# FPGAPower_Misc.net
KiCad netlist of a schematic drawn in Altium Designer
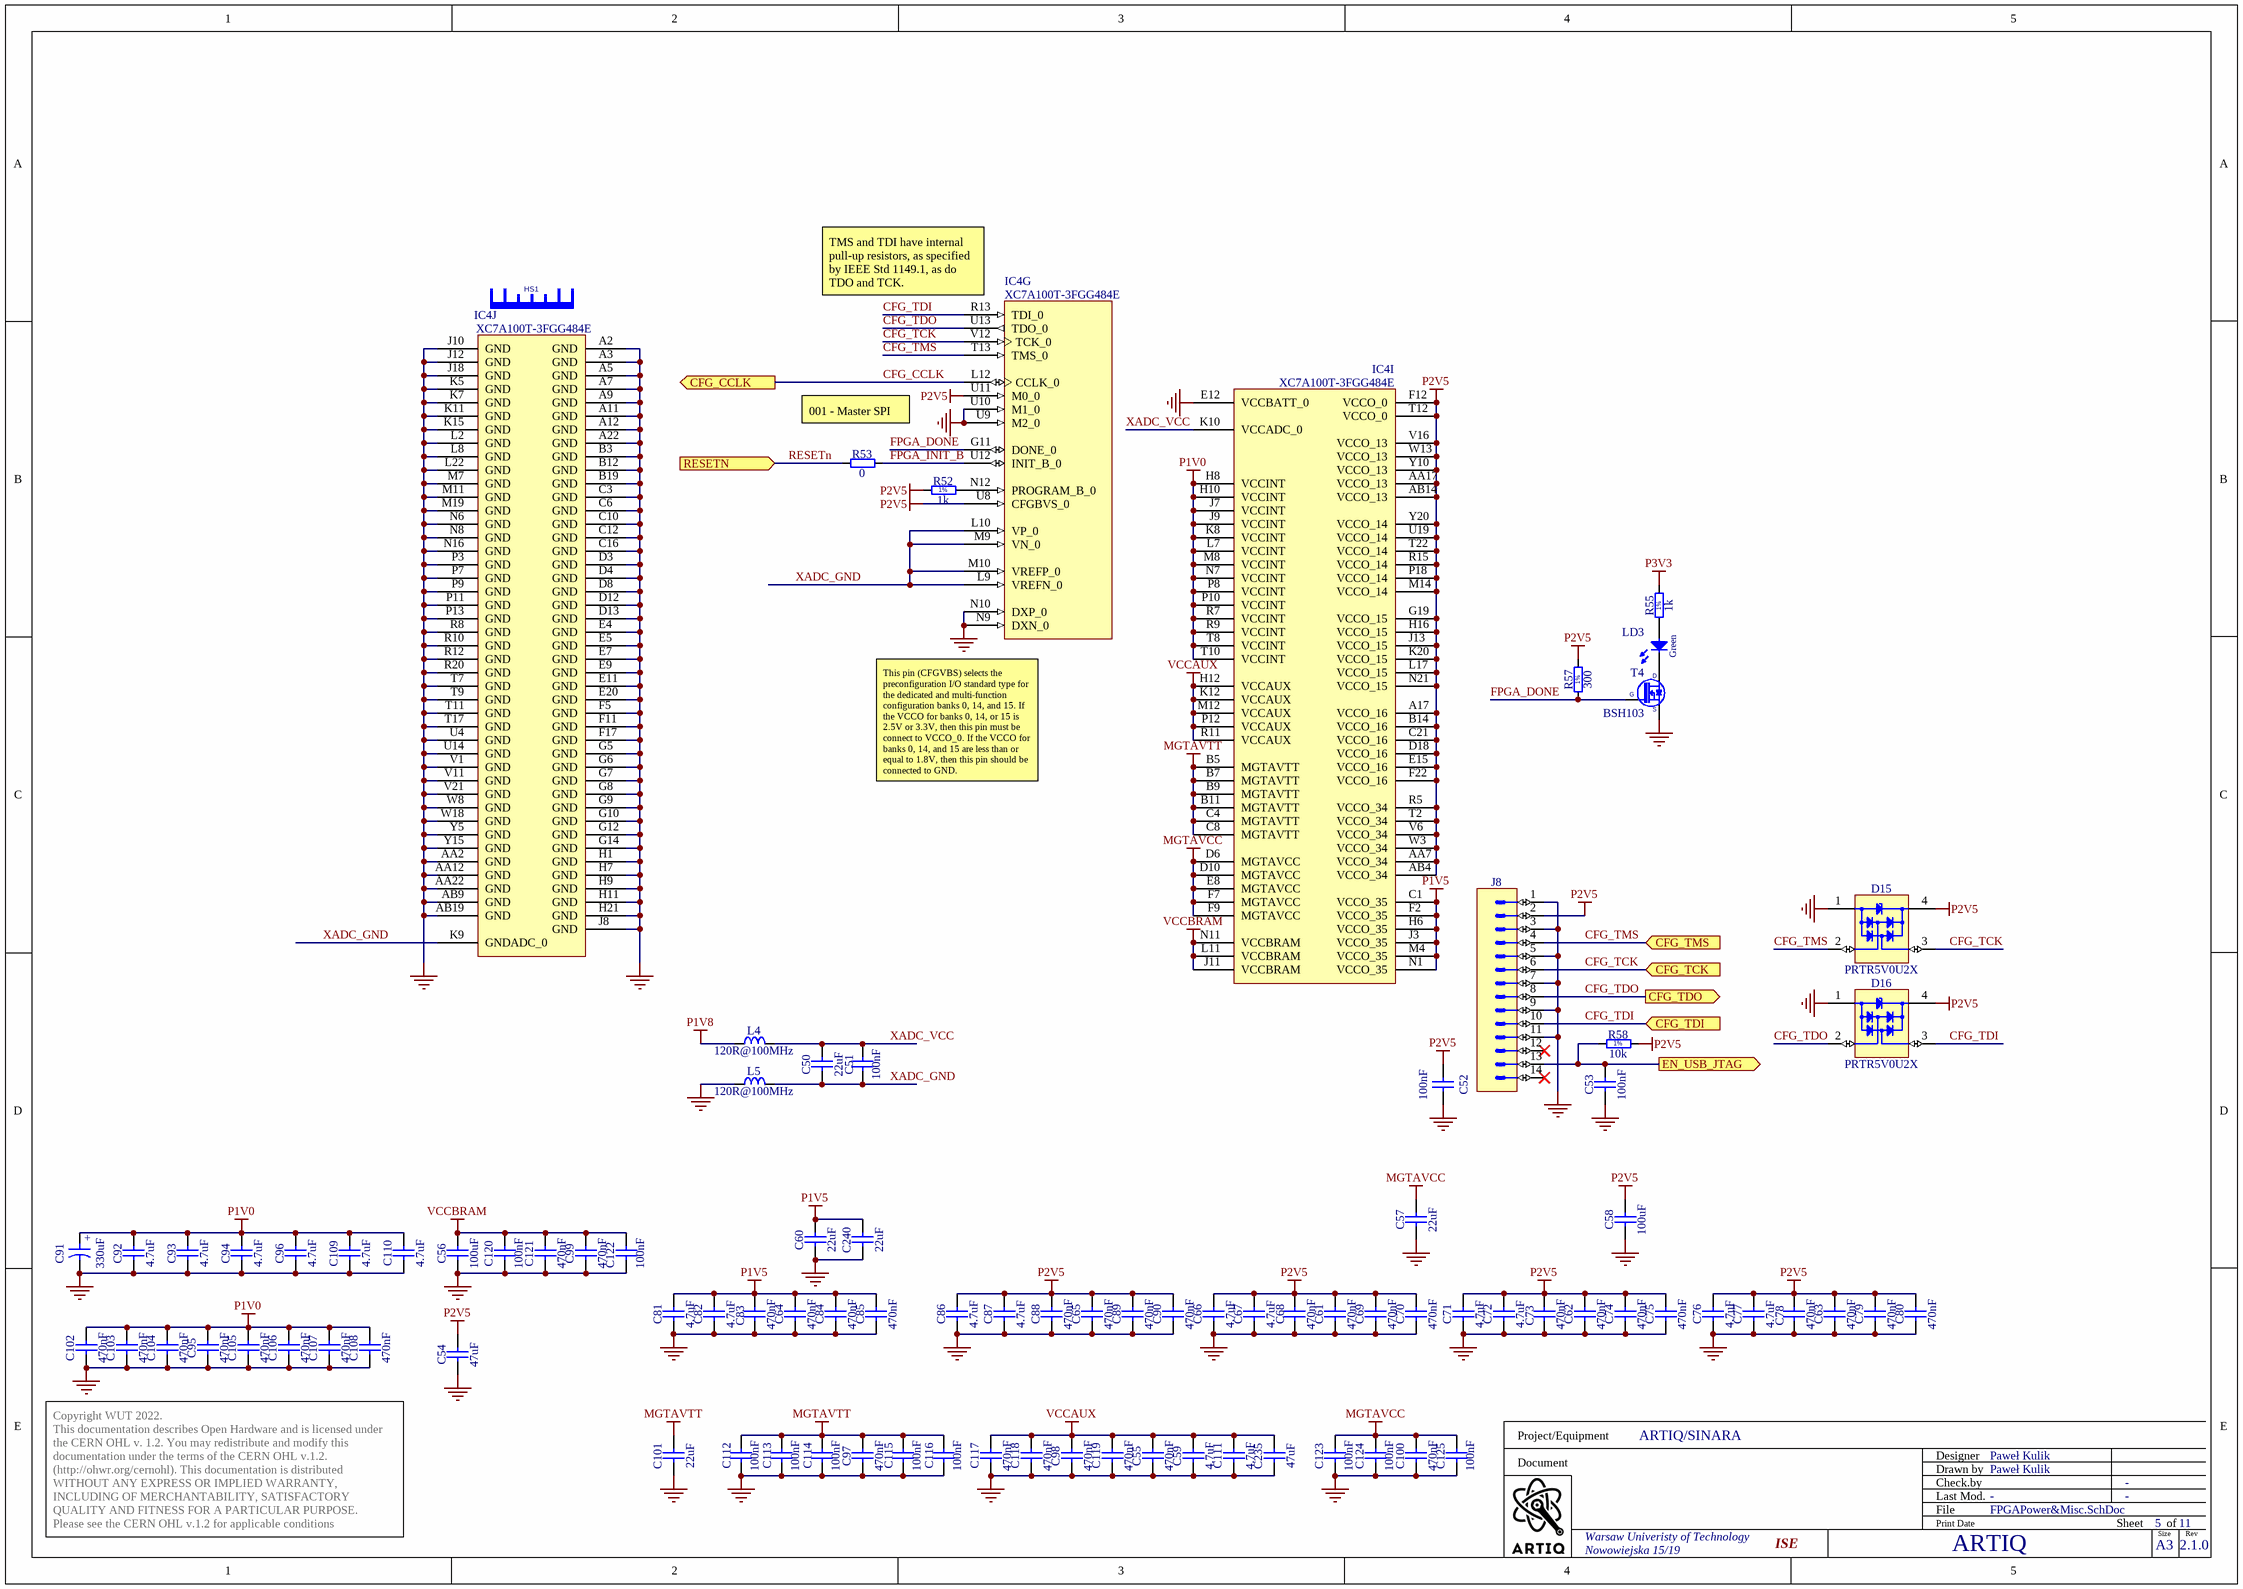
[diagram p0: FPGAPower&Misc.SchDoc]

(export (version "E")
  (design (tool "Eeschema 10.0.6"))
  (components
    (comp (ref "C50")
      (value "22uF")
      (footprint "CAPC1709X100N")
      (description "Non-polarised capacitor")
      (fields
        (field (name "PART NUMBER") "CC0603_22UF_6.3V_20%_X5R")
        (field (name "VOLTAGE") "6.3V")
        (field (name "AUTHOR") "CERN DEM JLC")
      )
      (libsource (lib "Capacitors") (part "Capacitor - non polarized"))
    )
    (comp (ref "C51")
      (value "100nF")
      (footprint "CAPC0603X33N")
      (description "Non-polarised capacitor")
      (fields
        (field (name "PART NUMBER") "CC0201_100NF_6.3V_10%_X5R")
        (field (name "VOLTAGE") "6.3V")
        (field (name "AUTHOR") "CERN DEM JLC")
      )
      (libsource (lib "Capacitors") (part "Capacitor - non polarized"))
    )
    (comp (ref "C52")
      (value "100nF")
      (footprint "CAPC0603X33N")
      (description "Non-polarised capacitor")
      (fields
        (field (name "PART NUMBER") "CC0201_100NF_6.3V_10%_X5R")
        (field (name "VOLTAGE") "6.3V")
        (field (name "AUTHOR") "CERN DEM JLC")
      )
      (libsource (lib "Capacitors") (part "Capacitor - non polarized"))
    )
    (comp (ref "C53")
      (value "100nF")
      (footprint "CAPC0603X33N")
      (description "Non-polarised capacitor")
      (fields
        (field (name "PART NUMBER") "CC0201_100NF_6.3V_10%_X5R")
        (field (name "VOLTAGE") "6.3V")
        (field (name "AUTHOR") "CERN DEM JLC")
      )
      (libsource (lib "Capacitors") (part "Capacitor - non polarized"))
    )
    (comp (ref "C54")
      (value "47uF")
      (footprint "CAPC3225X270N")
      (description "Non-polarised capacitor")
      (fields
        (field (name "PART NUMBER") "CC1210_47UF_10V_10%_X7R")
        (field (name "VOLTAGE") "10V")
        (field (name "AUTHOR") "CERN DEM BC")
      )
      (libsource (lib "Capacitors") (part "Capacitor - non polarized"))
    )
    (comp (ref "C55")
      (value "470nF")
      (footprint "CAPC0603X33N")
      (description "Non-polarised capacitor")
      (fields
        (field (name "PART NUMBER") "CC0201_470NF_4V_20%_X5R")
        (field (name "VOLTAGE") "4V")
        (field (name "AUTHOR") "CERN DEM JLC")
      )
      (libsource (lib "Capacitors") (part "Capacitor - non polarized"))
    )
    (comp (ref "C56")
      (value "100uF")
      (footprint "CAPC3225X270N")
      (description "Non-polarised capacitor")
      (fields
        (field (name "PART NUMBER") "CC1210_100UF_6.3V_20%_X5R")
        (field (name "VOLTAGE") "6.3V")
        (field (name "AUTHOR") "CERN DEM JLC")
      )
      (libsource (lib "Capacitors") (part "Capacitor - non polarized"))
    )
    (comp (ref "C57")
      (value "22uF")
      (footprint "CAPC1709X100N")
      (description "Non-polarised capacitor")
      (fields
        (field (name "PART NUMBER") "CC0603_22UF_6.3V_20%_X5R")
        (field (name "VOLTAGE") "6.3V")
        (field (name "AUTHOR") "CERN DEM JLC")
      )
      (libsource (lib "Capacitors") (part "Capacitor - non polarized"))
    )
    (comp (ref "C58")
      (value "100uF")
      (footprint "CAPC3225X270N")
      (description "Non-polarised capacitor")
      (fields
        (field (name "PART NUMBER") "CC1210_100UF_6.3V_20%_X5R")
        (field (name "VOLTAGE") "6.3V")
        (field (name "AUTHOR") "CERN DEM JLC")
      )
      (libsource (lib "Capacitors") (part "Capacitor - non polarized"))
    )
    (comp (ref "C59")
      (value "4.7uF")
      (footprint "CAPC2012X135N")
      (description "Non-polarised capacitor")
      (fields
        (field (name "MANUFACTURER") "GENERIC")
        (field (name "PART NUMBER") "CC0805_4.7UF_10V_10%_X5R")
        (field (name "AUTHOR") "CERN DEM JLC")
      )
      (libsource (lib "Capacitors") (part "Capacitor - non polarized"))
    )
    (comp (ref "C60")
      (value "22uF")
      (footprint "CAPC1709X100N")
      (description "Non-polarised capacitor")
      (fields
        (field (name "PART NUMBER") "CC0603_22UF_6.3V_20%_X5R")
        (field (name "VOLTAGE") "6.3V")
        (field (name "AUTHOR") "CERN DEM JLC")
      )
      (libsource (lib "Capacitors") (part "Capacitor - non polarized"))
    )
    (comp (ref "C61")
      (value "470nF")
      (footprint "CAPC0603X33N")
      (description "Non-polarised capacitor")
      (fields
        (field (name "PART NUMBER") "CC0201_470NF_4V_20%_X5R")
        (field (name "VOLTAGE") "4V")
        (field (name "AUTHOR") "CERN DEM JLC")
      )
      (libsource (lib "Capacitors") (part "Capacitor - non polarized"))
    )
    (comp (ref "C62")
      (value "470nF")
      (footprint "CAPC0603X33N")
      (description "Non-polarised capacitor")
      (fields
        (field (name "PART NUMBER") "CC0201_470NF_4V_20%_X5R")
        (field (name "VOLTAGE") "4V")
        (field (name "AUTHOR") "CERN DEM JLC")
      )
      (libsource (lib "Capacitors") (part "Capacitor - non polarized"))
    )
    (comp (ref "C63")
      (value "470nF")
      (footprint "CAPC0603X33N")
      (description "Non-polarised capacitor")
      (fields
        (field (name "PART NUMBER") "CC0201_470NF_4V_20%_X5R")
        (field (name "VOLTAGE") "4V")
        (field (name "AUTHOR") "CERN DEM JLC")
      )
      (libsource (lib "Capacitors") (part "Capacitor - non polarized"))
    )
    (comp (ref "C64")
      (value "470nF")
      (footprint "CAPC0603X33N")
      (description "Non-polarised capacitor")
      (fields
        (field (name "PART NUMBER") "CC0201_470NF_4V_20%_X5R")
        (field (name "VOLTAGE") "4V")
        (field (name "AUTHOR") "CERN DEM JLC")
      )
      (libsource (lib "Capacitors") (part "Capacitor - non polarized"))
    )
    (comp (ref "C65")
      (value "470nF")
      (footprint "CAPC0603X33N")
      (description "Non-polarised capacitor")
      (fields
        (field (name "PART NUMBER") "CC0201_470NF_4V_20%_X5R")
        (field (name "VOLTAGE") "4V")
        (field (name "AUTHOR") "CERN DEM JLC")
      )
      (libsource (lib "Capacitors") (part "Capacitor - non polarized"))
    )
    (comp (ref "C66")
      (value "4.7uF")
      (footprint "CAPC2012X135N")
      (description "Non-polarised capacitor")
      (fields
        (field (name "MANUFACTURER") "GENERIC")
        (field (name "PART NUMBER") "CC0805_4.7UF_10V_10%_X5R")
        (field (name "AUTHOR") "CERN DEM JLC")
      )
      (libsource (lib "Capacitors") (part "Capacitor - non polarized"))
    )
    (comp (ref "C67")
      (value "4.7uF")
      (footprint "CAPC2012X135N")
      (description "Non-polarised capacitor")
      (fields
        (field (name "MANUFACTURER") "GENERIC")
        (field (name "PART NUMBER") "CC0805_4.7UF_10V_10%_X5R")
        (field (name "AUTHOR") "CERN DEM JLC")
      )
      (libsource (lib "Capacitors") (part "Capacitor - non polarized"))
    )
    (comp (ref "C68")
      (value "470nF")
      (footprint "CAPC0603X33N")
      (description "Non-polarised capacitor")
      (fields
        (field (name "PART NUMBER") "CC0201_470NF_4V_20%_X5R")
        (field (name "VOLTAGE") "4V")
        (field (name "AUTHOR") "CERN DEM JLC")
      )
      (libsource (lib "Capacitors") (part "Capacitor - non polarized"))
    )
    (comp (ref "C69")
      (value "470nF")
      (footprint "CAPC0603X33N")
      (description "Non-polarised capacitor")
      (fields
        (field (name "PART NUMBER") "CC0201_470NF_4V_20%_X5R")
        (field (name "VOLTAGE") "4V")
        (field (name "AUTHOR") "CERN DEM JLC")
      )
      (libsource (lib "Capacitors") (part "Capacitor - non polarized"))
    )
    (comp (ref "C70")
      (value "470nF")
      (footprint "CAPC0603X33N")
      (description "Non-polarised capacitor")
      (fields
        (field (name "PART NUMBER") "CC0201_470NF_4V_20%_X5R")
        (field (name "VOLTAGE") "4V")
        (field (name "AUTHOR") "CERN DEM JLC")
      )
      (libsource (lib "Capacitors") (part "Capacitor - non polarized"))
    )
    (comp (ref "C71")
      (value "4.7uF")
      (footprint "CAPC2012X135N")
      (description "Non-polarised capacitor")
      (fields
        (field (name "MANUFACTURER") "GENERIC")
        (field (name "PART NUMBER") "CC0805_4.7UF_10V_10%_X5R")
        (field (name "AUTHOR") "CERN DEM JLC")
      )
      (libsource (lib "Capacitors") (part "Capacitor - non polarized"))
    )
    (comp (ref "C72")
      (value "4.7uF")
      (footprint "CAPC2012X135N")
      (description "Non-polarised capacitor")
      (fields
        (field (name "MANUFACTURER") "GENERIC")
        (field (name "PART NUMBER") "CC0805_4.7UF_10V_10%_X5R")
        (field (name "AUTHOR") "CERN DEM JLC")
      )
      (libsource (lib "Capacitors") (part "Capacitor - non polarized"))
    )
    (comp (ref "C73")
      (value "470nF")
      (footprint "CAPC0603X33N")
      (description "Non-polarised capacitor")
      (fields
        (field (name "PART NUMBER") "CC0201_470NF_4V_20%_X5R")
        (field (name "VOLTAGE") "4V")
        (field (name "AUTHOR") "CERN DEM JLC")
      )
      (libsource (lib "Capacitors") (part "Capacitor - non polarized"))
    )
    (comp (ref "C74")
      (value "470nF")
      (footprint "CAPC0603X33N")
      (description "Non-polarised capacitor")
      (fields
        (field (name "PART NUMBER") "CC0201_470NF_4V_20%_X5R")
        (field (name "VOLTAGE") "4V")
        (field (name "AUTHOR") "CERN DEM JLC")
      )
      (libsource (lib "Capacitors") (part "Capacitor - non polarized"))
    )
    (comp (ref "C75")
      (value "470nF")
      (footprint "CAPC0603X33N")
      (description "Non-polarised capacitor")
      (fields
        (field (name "PART NUMBER") "CC0201_470NF_4V_20%_X5R")
        (field (name "VOLTAGE") "4V")
        (field (name "AUTHOR") "CERN DEM JLC")
      )
      (libsource (lib "Capacitors") (part "Capacitor - non polarized"))
    )
    (comp (ref "C76")
      (value "4.7uF")
      (footprint "CAPC2012X135N")
      (description "Non-polarised capacitor")
      (fields
        (field (name "MANUFACTURER") "GENERIC")
        (field (name "PART NUMBER") "CC0805_4.7UF_10V_10%_X5R")
        (field (name "AUTHOR") "CERN DEM JLC")
      )
      (libsource (lib "Capacitors") (part "Capacitor - non polarized"))
    )
    (comp (ref "C77")
      (value "4.7uF")
      (footprint "CAPC2012X135N")
      (description "Non-polarised capacitor")
      (fields
        (field (name "MANUFACTURER") "GENERIC")
        (field (name "PART NUMBER") "CC0805_4.7UF_10V_10%_X5R")
        (field (name "AUTHOR") "CERN DEM JLC")
      )
      (libsource (lib "Capacitors") (part "Capacitor - non polarized"))
    )
    (comp (ref "C78")
      (value "470nF")
      (footprint "CAPC0603X33N")
      (description "Non-polarised capacitor")
      (fields
        (field (name "PART NUMBER") "CC0201_470NF_4V_20%_X5R")
        (field (name "VOLTAGE") "4V")
        (field (name "AUTHOR") "CERN DEM JLC")
      )
      (libsource (lib "Capacitors") (part "Capacitor - non polarized"))
    )
    (comp (ref "C79")
      (value "470nF")
      (footprint "CAPC0603X33N")
      (description "Non-polarised capacitor")
      (fields
        (field (name "PART NUMBER") "CC0201_470NF_4V_20%_X5R")
        (field (name "VOLTAGE") "4V")
        (field (name "AUTHOR") "CERN DEM JLC")
      )
      (libsource (lib "Capacitors") (part "Capacitor - non polarized"))
    )
    (comp (ref "C80")
      (value "470nF")
      (footprint "CAPC0603X33N")
      (description "Non-polarised capacitor")
      (fields
        (field (name "PART NUMBER") "CC0201_470NF_4V_20%_X5R")
        (field (name "VOLTAGE") "4V")
        (field (name "AUTHOR") "CERN DEM JLC")
      )
      (libsource (lib "Capacitors") (part "Capacitor - non polarized"))
    )
    (comp (ref "C81")
      (value "4.7uF")
      (footprint "CAPC2012X135N")
      (description "Non-polarised capacitor")
      (fields
        (field (name "MANUFACTURER") "GENERIC")
        (field (name "PART NUMBER") "CC0805_4.7UF_10V_10%_X5R")
        (field (name "AUTHOR") "CERN DEM JLC")
      )
      (libsource (lib "Capacitors") (part "Capacitor - non polarized"))
    )
    (comp (ref "C82")
      (value "4.7uF")
      (footprint "CAPC2012X135N")
      (description "Non-polarised capacitor")
      (fields
        (field (name "MANUFACTURER") "GENERIC")
        (field (name "PART NUMBER") "CC0805_4.7UF_10V_10%_X5R")
        (field (name "AUTHOR") "CERN DEM JLC")
      )
      (libsource (lib "Capacitors") (part "Capacitor - non polarized"))
    )
    (comp (ref "C83")
      (value "470nF")
      (footprint "CAPC0603X33N")
      (description "Non-polarised capacitor")
      (fields
        (field (name "PART NUMBER") "CC0201_470NF_4V_20%_X5R")
        (field (name "VOLTAGE") "4V")
        (field (name "AUTHOR") "CERN DEM JLC")
      )
      (libsource (lib "Capacitors") (part "Capacitor - non polarized"))
    )
    (comp (ref "C84")
      (value "470nF")
      (footprint "CAPC0603X33N")
      (description "Non-polarised capacitor")
      (fields
        (field (name "PART NUMBER") "CC0201_470NF_4V_20%_X5R")
        (field (name "VOLTAGE") "4V")
        (field (name "AUTHOR") "CERN DEM JLC")
      )
      (libsource (lib "Capacitors") (part "Capacitor - non polarized"))
    )
    (comp (ref "C85")
      (value "470nF")
      (footprint "CAPC0603X33N")
      (description "Non-polarised capacitor")
      (fields
        (field (name "PART NUMBER") "CC0201_470NF_4V_20%_X5R")
        (field (name "VOLTAGE") "4V")
        (field (name "AUTHOR") "CERN DEM JLC")
      )
      (libsource (lib "Capacitors") (part "Capacitor - non polarized"))
    )
    (comp (ref "C86")
      (value "4.7uF")
      (footprint "CAPC2012X135N")
      (description "Non-polarised capacitor")
      (fields
        (field (name "MANUFACTURER") "GENERIC")
        (field (name "PART NUMBER") "CC0805_4.7UF_10V_10%_X5R")
        (field (name "AUTHOR") "CERN DEM JLC")
      )
      (libsource (lib "Capacitors") (part "Capacitor - non polarized"))
    )
    (comp (ref "C87")
      (value "4.7uF")
      (footprint "CAPC2012X135N")
      (description "Non-polarised capacitor")
      (fields
        (field (name "MANUFACTURER") "GENERIC")
        (field (name "PART NUMBER") "CC0805_4.7UF_10V_10%_X5R")
        (field (name "AUTHOR") "CERN DEM JLC")
      )
      (libsource (lib "Capacitors") (part "Capacitor - non polarized"))
    )
    (comp (ref "C88")
      (value "470nF")
      (footprint "CAPC0603X33N")
      (description "Non-polarised capacitor")
      (fields
        (field (name "PART NUMBER") "CC0201_470NF_4V_20%_X5R")
        (field (name "VOLTAGE") "4V")
        (field (name "AUTHOR") "CERN DEM JLC")
      )
      (libsource (lib "Capacitors") (part "Capacitor - non polarized"))
    )
    (comp (ref "C89")
      (value "470nF")
      (footprint "CAPC0603X33N")
      (description "Non-polarised capacitor")
      (fields
        (field (name "PART NUMBER") "CC0201_470NF_4V_20%_X5R")
        (field (name "VOLTAGE") "4V")
        (field (name "AUTHOR") "CERN DEM JLC")
      )
      (libsource (lib "Capacitors") (part "Capacitor - non polarized"))
    )
    (comp (ref "C90")
      (value "470nF")
      (footprint "CAPC0603X33N")
      (description "Non-polarised capacitor")
      (fields
        (field (name "PART NUMBER") "CC0201_470NF_4V_20%_X5R")
        (field (name "VOLTAGE") "4V")
        (field (name "AUTHOR") "CERN DEM JLC")
      )
      (libsource (lib "Capacitors") (part "Capacitor - non polarized"))
    )
    (comp (ref "C91")
      (value "330uF")
      (footprint "CAPMP7343X190N")
      (description "Polarised capacitor")
      (fields
        (field (name "PART NUMBER") "CTE7343-19_330UF_2.5V_20%_LESR0025_KEMET_T520")
        (field (name "VOLTAGE") "2.5V")
        (field (name "AUTHOR") "CERN DEM MR")
      )
      (libsource (lib "Capacitors") (part "Capacitor - polarized"))
    )
    (comp (ref "C92")
      (value "4.7uF")
      (footprint "CAPC2012X135N")
      (description "Non-polarised capacitor")
      (fields
        (field (name "MANUFACTURER") "GENERIC")
        (field (name "PART NUMBER") "CC0805_4.7UF_10V_10%_X5R")
        (field (name "AUTHOR") "CERN DEM JLC")
      )
      (libsource (lib "Capacitors") (part "Capacitor - non polarized"))
    )
    (comp (ref "C93")
      (value "4.7uF")
      (footprint "CAPC2012X135N")
      (description "Non-polarised capacitor")
      (fields
        (field (name "MANUFACTURER") "GENERIC")
        (field (name "PART NUMBER") "CC0805_4.7UF_10V_10%_X5R")
        (field (name "AUTHOR") "CERN DEM JLC")
      )
      (libsource (lib "Capacitors") (part "Capacitor - non polarized"))
    )
    (comp (ref "C94")
      (value "4.7uF")
      (footprint "CAPC2012X135N")
      (description "Non-polarised capacitor")
      (fields
        (field (name "MANUFACTURER") "GENERIC")
        (field (name "PART NUMBER") "CC0805_4.7UF_10V_10%_X5R")
        (field (name "AUTHOR") "CERN DEM JLC")
      )
      (libsource (lib "Capacitors") (part "Capacitor - non polarized"))
    )
    (comp (ref "C95")
      (value "470nF")
      (footprint "CAPC0603X33N")
      (description "Non-polarised capacitor")
      (fields
        (field (name "PART NUMBER") "CC0201_470NF_4V_20%_X5R")
        (field (name "VOLTAGE") "4V")
        (field (name "AUTHOR") "CERN DEM JLC")
      )
      (libsource (lib "Capacitors") (part "Capacitor - non polarized"))
    )
    (comp (ref "C96")
      (value "4.7uF")
      (footprint "CAPC2012X135N")
      (description "Non-polarised capacitor")
      (fields
        (field (name "MANUFACTURER") "GENERIC")
        (field (name "PART NUMBER") "CC0805_4.7UF_10V_10%_X5R")
        (field (name "AUTHOR") "CERN DEM JLC")
      )
      (libsource (lib "Capacitors") (part "Capacitor - non polarized"))
    )
    (comp (ref "C97")
      (value "470nF")
      (footprint "CAPC0603X33N")
      (description "Non-polarised capacitor")
      (fields
        (field (name "PART NUMBER") "CC0201_470NF_4V_20%_X5R")
        (field (name "VOLTAGE") "4V")
        (field (name "AUTHOR") "CERN DEM JLC")
      )
      (libsource (lib "Capacitors") (part "Capacitor - non polarized"))
    )
    (comp (ref "C98")
      (value "470nF")
      (footprint "CAPC0603X33N")
      (description "Non-polarised capacitor")
      (fields
        (field (name "PART NUMBER") "CC0201_470NF_4V_20%_X5R")
        (field (name "VOLTAGE") "4V")
        (field (name "AUTHOR") "CERN DEM JLC")
      )
      (libsource (lib "Capacitors") (part "Capacitor - non polarized"))
    )
    (comp (ref "C99")
      (value "470nF")
      (footprint "CAPC0603X33N")
      (description "Non-polarised capacitor")
      (fields
        (field (name "PART NUMBER") "CC0201_470NF_4V_20%_X5R")
        (field (name "VOLTAGE") "4V")
        (field (name "AUTHOR") "CERN DEM JLC")
      )
      (libsource (lib "Capacitors") (part "Capacitor - non polarized"))
    )
    (comp (ref "C100")
      (value "470nF")
      (footprint "CAPC0603X33N")
      (description "Non-polarised capacitor")
      (fields
        (field (name "PART NUMBER") "CC0201_470NF_4V_20%_X5R")
        (field (name "VOLTAGE") "4V")
        (field (name "AUTHOR") "CERN DEM JLC")
      )
      (libsource (lib "Capacitors") (part "Capacitor - non polarized"))
    )
    (comp (ref "C101")
      (value "22uF")
      (footprint "CAPC1709X100N")
      (description "Non-polarised capacitor")
      (fields
        (field (name "PART NUMBER") "CC0603_22UF_6.3V_20%_X5R")
        (field (name "VOLTAGE") "6.3V")
        (field (name "AUTHOR") "CERN DEM JLC")
      )
      (libsource (lib "Capacitors") (part "Capacitor - non polarized"))
    )
    (comp (ref "C102")
      (value "470nF")
      (footprint "CAPC0603X33N")
      (description "Non-polarised capacitor")
      (fields
        (field (name "PART NUMBER") "CC0201_470NF_4V_20%_X5R")
        (field (name "VOLTAGE") "4V")
        (field (name "AUTHOR") "CERN DEM JLC")
      )
      (libsource (lib "Capacitors") (part "Capacitor - non polarized"))
    )
    (comp (ref "C103")
      (value "470nF")
      (footprint "CAPC0603X33N")
      (description "Non-polarised capacitor")
      (fields
        (field (name "PART NUMBER") "CC0201_470NF_4V_20%_X5R")
        (field (name "VOLTAGE") "4V")
        (field (name "AUTHOR") "CERN DEM JLC")
      )
      (libsource (lib "Capacitors") (part "Capacitor - non polarized"))
    )
    (comp (ref "C104")
      (value "470nF")
      (footprint "CAPC0603X33N")
      (description "Non-polarised capacitor")
      (fields
        (field (name "PART NUMBER") "CC0201_470NF_4V_20%_X5R")
        (field (name "VOLTAGE") "4V")
        (field (name "AUTHOR") "CERN DEM JLC")
      )
      (libsource (lib "Capacitors") (part "Capacitor - non polarized"))
    )
    (comp (ref "C105")
      (value "470nF")
      (footprint "CAPC0603X33N")
      (description "Non-polarised capacitor")
      (fields
        (field (name "PART NUMBER") "CC0201_470NF_4V_20%_X5R")
        (field (name "VOLTAGE") "4V")
        (field (name "AUTHOR") "CERN DEM JLC")
      )
      (libsource (lib "Capacitors") (part "Capacitor - non polarized"))
    )
    (comp (ref "C106")
      (value "470nF")
      (footprint "CAPC0603X33N")
      (description "Non-polarised capacitor")
      (fields
        (field (name "PART NUMBER") "CC0201_470NF_4V_20%_X5R")
        (field (name "VOLTAGE") "4V")
        (field (name "AUTHOR") "CERN DEM JLC")
      )
      (libsource (lib "Capacitors") (part "Capacitor - non polarized"))
    )
    (comp (ref "C107")
      (value "470nF")
      (footprint "CAPC0603X33N")
      (description "Non-polarised capacitor")
      (fields
        (field (name "PART NUMBER") "CC0201_470NF_4V_20%_X5R")
        (field (name "VOLTAGE") "4V")
        (field (name "AUTHOR") "CERN DEM JLC")
      )
      (libsource (lib "Capacitors") (part "Capacitor - non polarized"))
    )
    (comp (ref "C108")
      (value "470nF")
      (footprint "CAPC0603X33N")
      (description "Non-polarised capacitor")
      (fields
        (field (name "PART NUMBER") "CC0201_470NF_4V_20%_X5R")
        (field (name "VOLTAGE") "4V")
        (field (name "AUTHOR") "CERN DEM JLC")
      )
      (libsource (lib "Capacitors") (part "Capacitor - non polarized"))
    )
    (comp (ref "C109")
      (value "4.7uF")
      (footprint "CAPC2012X135N")
      (description "Non-polarised capacitor")
      (fields
        (field (name "MANUFACTURER") "GENERIC")
        (field (name "PART NUMBER") "CC0805_4.7UF_10V_10%_X5R")
        (field (name "AUTHOR") "CERN DEM JLC")
      )
      (libsource (lib "Capacitors") (part "Capacitor - non polarized"))
    )
    (comp (ref "C110")
      (value "4.7uF")
      (footprint "CAPC2012X135N")
      (description "Non-polarised capacitor")
      (fields
        (field (name "MANUFACTURER") "GENERIC")
        (field (name "PART NUMBER") "CC0805_4.7UF_10V_10%_X5R")
        (field (name "AUTHOR") "CERN DEM JLC")
      )
      (libsource (lib "Capacitors") (part "Capacitor - non polarized"))
    )
    (comp (ref "C111")
      (value "4.7uF")
      (footprint "CAPC2012X135N")
      (description "Non-polarised capacitor")
      (fields
        (field (name "MANUFACTURER") "GENERIC")
        (field (name "PART NUMBER") "CC0805_4.7UF_10V_10%_X5R")
        (field (name "AUTHOR") "CERN DEM JLC")
      )
      (libsource (lib "Capacitors") (part "Capacitor - non polarized"))
    )
    (comp (ref "C112")
      (value "100nF")
      (footprint "CAPC0603X33N")
      (description "Non-polarised capacitor")
      (fields
        (field (name "PART NUMBER") "CC0201_100NF_6.3V_10%_X5R")
        (field (name "VOLTAGE") "6.3V")
        (field (name "AUTHOR") "CERN DEM JLC")
      )
      (libsource (lib "Capacitors") (part "Capacitor - non polarized"))
    )
    (comp (ref "C113")
      (value "100nF")
      (footprint "CAPC0603X33N")
      (description "Non-polarised capacitor")
      (fields
        (field (name "PART NUMBER") "CC0201_100NF_6.3V_10%_X5R")
        (field (name "VOLTAGE") "6.3V")
        (field (name "AUTHOR") "CERN DEM JLC")
      )
      (libsource (lib "Capacitors") (part "Capacitor - non polarized"))
    )
    (comp (ref "C114")
      (value "100nF")
      (footprint "CAPC0603X33N")
      (description "Non-polarised capacitor")
      (fields
        (field (name "PART NUMBER") "CC0201_100NF_6.3V_10%_X5R")
        (field (name "VOLTAGE") "6.3V")
        (field (name "AUTHOR") "CERN DEM JLC")
      )
      (libsource (lib "Capacitors") (part "Capacitor - non polarized"))
    )
    (comp (ref "C115")
      (value "100nF")
      (footprint "CAPC0603X33N")
      (description "Non-polarised capacitor")
      (fields
        (field (name "PART NUMBER") "CC0201_100NF_6.3V_10%_X5R")
        (field (name "VOLTAGE") "6.3V")
        (field (name "AUTHOR") "CERN DEM JLC")
      )
      (libsource (lib "Capacitors") (part "Capacitor - non polarized"))
    )
    (comp (ref "C116")
      (value "100nF")
      (footprint "CAPC0603X33N")
      (description "Non-polarised capacitor")
      (fields
        (field (name "PART NUMBER") "CC0201_100NF_6.3V_10%_X5R")
        (field (name "VOLTAGE") "6.3V")
        (field (name "AUTHOR") "CERN DEM JLC")
      )
      (libsource (lib "Capacitors") (part "Capacitor - non polarized"))
    )
    (comp (ref "C117")
      (value "470nF")
      (footprint "CAPC0603X33N")
      (description "Non-polarised capacitor")
      (fields
        (field (name "PART NUMBER") "CC0201_470NF_4V_20%_X5R")
        (field (name "VOLTAGE") "4V")
        (field (name "AUTHOR") "CERN DEM JLC")
      )
      (libsource (lib "Capacitors") (part "Capacitor - non polarized"))
    )
    (comp (ref "C118")
      (value "470nF")
      (footprint "CAPC0603X33N")
      (description "Non-polarised capacitor")
      (fields
        (field (name "PART NUMBER") "CC0201_470NF_4V_20%_X5R")
        (field (name "VOLTAGE") "4V")
        (field (name "AUTHOR") "CERN DEM JLC")
      )
      (libsource (lib "Capacitors") (part "Capacitor - non polarized"))
    )
    (comp (ref "C119")
      (value "470nF")
      (footprint "CAPC0603X33N")
      (description "Non-polarised capacitor")
      (fields
        (field (name "PART NUMBER") "CC0201_470NF_4V_20%_X5R")
        (field (name "VOLTAGE") "4V")
        (field (name "AUTHOR") "CERN DEM JLC")
      )
      (libsource (lib "Capacitors") (part "Capacitor - non polarized"))
    )
    (comp (ref "C120")
      (value "100nF")
      (footprint "CAPC0603X33N")
      (description "Non-polarised capacitor")
      (fields
        (field (name "PART NUMBER") "CC0201_100NF_6.3V_10%_X5R")
        (field (name "VOLTAGE") "6.3V")
        (field (name "AUTHOR") "CERN DEM JLC")
      )
      (libsource (lib "Capacitors") (part "Capacitor - non polarized"))
    )
    (comp (ref "C121")
      (value "470nF")
      (footprint "CAPC0603X33N")
      (description "Non-polarised capacitor")
      (fields
        (field (name "PART NUMBER") "CC0201_470NF_4V_20%_X5R")
        (field (name "VOLTAGE") "4V")
        (field (name "AUTHOR") "CERN DEM JLC")
      )
      (libsource (lib "Capacitors") (part "Capacitor - non polarized"))
    )
    (comp (ref "C122")
      (value "100nF")
      (footprint "CAPC0603X33N")
      (description "Non-polarised capacitor")
      (fields
        (field (name "PART NUMBER") "CC0201_100NF_6.3V_10%_X5R")
        (field (name "VOLTAGE") "6.3V")
        (field (name "AUTHOR") "CERN DEM JLC")
      )
      (libsource (lib "Capacitors") (part "Capacitor - non polarized"))
    )
    (comp (ref "C123")
      (value "100nF")
      (footprint "CAPC0603X33N")
      (description "Non-polarised capacitor")
      (fields
        (field (name "PART NUMBER") "CC0201_100NF_6.3V_10%_X5R")
        (field (name "VOLTAGE") "6.3V")
        (field (name "AUTHOR") "CERN DEM JLC")
      )
      (libsource (lib "Capacitors") (part "Capacitor - non polarized"))
    )
    (comp (ref "C124")
      (value "100nF")
      (footprint "CAPC0603X33N")
      (description "Non-polarised capacitor")
      (fields
        (field (name "PART NUMBER") "CC0201_100NF_6.3V_10%_X5R")
        (field (name "VOLTAGE") "6.3V")
        (field (name "AUTHOR") "CERN DEM JLC")
      )
      (libsource (lib "Capacitors") (part "Capacitor - non polarized"))
    )
    (comp (ref "C125")
      (value "100nF")
      (footprint "CAPC0603X33N")
      (description "Non-polarised capacitor")
      (fields
        (field (name "PART NUMBER") "CC0201_100NF_6.3V_10%_X5R")
        (field (name "VOLTAGE") "6.3V")
        (field (name "AUTHOR") "CERN DEM JLC")
      )
      (libsource (lib "Capacitors") (part "Capacitor - non polarized"))
    )
    (comp (ref "C235")
      (value "47uF")
      (footprint "CAPC3225X270N")
      (description "Non-polarised capacitor")
      (fields
        (field (name "PART NUMBER") "CC1210_47UF_10V_10%_X7R")
        (field (name "VOLTAGE") "10V")
        (field (name "AUTHOR") "CERN DEM BC")
      )
      (libsource (lib "Capacitors") (part "Capacitor - non polarized"))
    )
    (comp (ref "C240")
      (value "22uF")
      (footprint "CAPC1709X100N")
      (description "Non-polarised capacitor")
      (fields
        (field (name "PART NUMBER") "CC0603_22UF_6.3V_20%_X5R")
        (field (name "VOLTAGE") "6.3V")
        (field (name "AUTHOR") "CERN DEM JLC")
      )
      (libsource (lib "Capacitors") (part "Capacitor - non polarized"))
    )
    (comp (ref "D15")
      (value "PRTR5V0U2X")
      (footprint "SOT190P230X110-4N")
      (description "Ultra Low Capacitance Double Rail-to-Rail ESD Protection Diode")
      (fields
        (field (name "VOLTAGE") "5.5V")
        (field (name "MANUFACTURER") "NXP SEMICONDUCTORS")
        (field (name "AUTHOR") "CERN DEM JLC")
      )
      (libsource (lib "ICs And Semiconductors") (part "PRTR5V0U2X"))
    )
    (comp (ref "D16")
      (value "PRTR5V0U2X")
      (footprint "SOT190P230X110-4N")
      (description "Ultra Low Capacitance Double Rail-to-Rail ESD Protection Diode")
      (fields
        (field (name "VOLTAGE") "5.5V")
        (field (name "MANUFACTURER") "NXP SEMICONDUCTORS")
        (field (name "AUTHOR") "CERN DEM JLC")
      )
      (libsource (lib "ICs And Semiconductors") (part "PRTR5V0U2X"))
    )
    (comp (ref "HS1")
      (value "RADIAN_FI23")
      (footprint "RADIAN_FI23")
      (description "Heat Sink Without Pad")
      (fields
        (field (name "MANUFACTURER") "Radian Thermal Products, Inc.")
        (field (name "MANUFACTURER PART NUMBER") "FI23+BU+T725")
      )
      (libsource (lib "Schlib1") (part "RADIAN_FI23"))
    )
    (comp (ref "IC4")
      (value "XC7A100T-3FGG484E")
      (footprint "BGA484C100P22X22_2300X2300X260")
      (fields (field (name "MANUFACTURER") "XILINX") (field (name "AUTHOR") "CERN DEM BC"))
      (libsource (lib "") (part "XC7A100T-3FGG484E_1"))
    )
    (comp (ref "J8")
      (value "Milli-Grid™")
      (footprint "MOLEX_87832-1420")
      (description "Connector 14 Male")
      (fields
        (field (name "PART NUMBER") "MOLEX_87832-1420")
        (field (name "MANUFACTURER") "MOLEX")
        (field (name "AUTHOR") "CERN DEM JLC")
      )
      (libsource (lib "Connectors") (part "Connector 14 Male"))
    )
    (comp (ref "L4")
      (value "120R@100MHz")
      (footprint "INDC1608X65N")
      (description "Inductor")
      (fields
        (field (name "PART NUMBER") "IND0603_MURATA_BLM18SG121TN1D")
        (field (name "POWER") "3A")
        (field (name "AUTHOR") "CERN DEM JLC")
      )
      (libsource (lib "Inductors & Transformers") (part "Inductor"))
    )
    (comp (ref "L5")
      (value "120R@100MHz")
      (footprint "INDC1608X65N")
      (description "Inductor")
      (fields
        (field (name "PART NUMBER") "IND0603_MURATA_BLM18SG121TN1D")
        (field (name "POWER") "3A")
        (field (name "AUTHOR") "CERN DEM JLC")
      )
      (libsource (lib "Inductors & Transformers") (part "Inductor"))
    )
    (comp (ref "LD3")
      (value "Green")
      (footprint "LED_KINGBRIGHT_KPH-1608CGCK")
      (description "LED Green 1C 2A")
      (fields
        (field (name "MANUFACTURER PART NUMBER") "KPH-1608CGCK")
        (field (name "PART NUMBER") "LED_KINGBRIGHT_KPH-1608CGCK")
        (field (name "AUTHOR") "CERN DEM JLC")
      )
      (libsource (lib "ICs And Semiconductors") (part "LED Green 1C 2A"))
    )
    (comp (ref "R52")
      (value "1k")
      (footprint "RESC1005X40N")
      (description "Resistor - 1%")
      (fields
        (field (name "PART NUMBER") "R0402_1K_1%_0.0625W_100PPM")
        (field (name "POWER") "0.0625W")
        (field (name "AUTHOR") "CERN DEM JLC")
      )
      (libsource (lib "Resistors") (part "Resistor - 1%"))
    )
    (comp (ref "R53")
      (value "0")
      (footprint "RESC1005X40N")
      (description "Resistor")
      (fields
        (field (name "PART NUMBER") "R0402_0R_JUMPER")
        (field (name "MANUFACTURER") "GENERIC")
        (field (name "AUTHOR") "CERN DEM JLC")
      )
      (libsource (lib "Resistors") (part "Resistor"))
    )
    (comp (ref "R55")
      (value "1k")
      (footprint "RESC1005X40N")
      (description "Resistor - 1%")
      (fields
        (field (name "PART NUMBER") "R0402_1K_1%_0.0625W_100PPM")
        (field (name "POWER") "0.0625W")
        (field (name "AUTHOR") "CERN DEM JLC")
      )
      (libsource (lib "Resistors") (part "Resistor - 1%"))
    )
    (comp (ref "R57")
      (value "300")
      (footprint "RESC1005X40N")
      (description "Resistor - 1%")
      (fields
        (field (name "PART NUMBER") "R0402_300R_1%_0.0625W_100PPM")
        (field (name "POWER") "0.0625W")
        (field (name "AUTHOR") "CERN DEM JLC")
      )
      (libsource (lib "Resistors") (part "Resistor - 1%"))
    )
    (comp (ref "R58")
      (value "10k")
      (footprint "RESC1005X40N")
      (description "Resistor - 1%")
      (fields
        (field (name "PART NUMBER") "R0402_10K_1%_0.0625W_100PPM")
        (field (name "POWER") "0.0625W")
        (field (name "AUTHOR") "CERN DEM JLC")
      )
      (libsource (lib "Resistors") (part "Resistor - 1%"))
    )
    (comp (ref "T4")
      (value "BSH103")
      (footprint "SOT95P230X110-3N")
      (description "N-CHANNEL MOSFET WITH DIODE")
      (fields (field (name "MANUFACTURER") "NEXPERIA") (field (name "AUTHOR") "CERN DEM JLC"))
      (libsource (lib "ICs And Semiconductors") (part "N-MOSFET-D 1G 2S 3D"))
    )
  )
  (nets
    (net (code "1") (name "/CFG_CCLK") (class "Default")
      (node (ref "IC4") (pin "L12") (pinfunction "CCLK_0_L12") (pintype "bidirectional"))
    )
    (net (code "2") (name "/CFG_TCK") (class "Default")
      (node (ref "D15") (pin "3") (pinfunction "I/O2_3") (pintype "bidirectional"))
      (node (ref "IC4") (pin "V12") (pinfunction "TCK_0_V12") (pintype "input"))
      (node (ref "J8") (pin "6") (pinfunction "6_6") (pintype "bidirectional"))
    )
    (net (code "3") (name "/CFG_TDI") (class "Default")
      (node (ref "D16") (pin "3") (pinfunction "I/O2_3") (pintype "bidirectional"))
      (node (ref "IC4") (pin "R13") (pinfunction "TDI_0_R13") (pintype "input"))
      (node (ref "J8") (pin "10") (pinfunction "10_10") (pintype "bidirectional"))
    )
    (net (code "4") (name "/CFG_TDO") (class "Default")
      (node (ref "D16") (pin "2") (pinfunction "I/O1_2") (pintype "bidirectional"))
      (node (ref "IC4") (pin "U13") (pinfunction "TDO_0_U13") (pintype "output"))
      (node (ref "J8") (pin "8") (pinfunction "8_8") (pintype "bidirectional"))
    )
    (net (code "5") (name "/CFG_TMS") (class "Default")
      (node (ref "D15") (pin "2") (pinfunction "I/O1_2") (pintype "bidirectional"))
      (node (ref "IC4") (pin "T13") (pinfunction "TMS_0_T13") (pintype "input"))
      (node (ref "J8") (pin "4") (pinfunction "4_4") (pintype "bidirectional"))
    )
    (net (code "6") (name "/EN_USB_JTAG") (class "Default")
      (node (ref "C53") (pin "2") (pinfunction "2_2") (pintype "passive"))
      (node (ref "J8") (pin "13") (pinfunction "13_13") (pintype "bidirectional"))
      (node (ref "R58") (pin "1") (pinfunction "1_1") (pintype "passive"))
    )
    (net (code "7") (name "/FPGA_DONE") (class "Default")
      (node (ref "IC4") (pin "G11") (pinfunction "DONE_0_G11") (pintype "bidirectional"))
      (node (ref "R57") (pin "1") (pinfunction "1_1") (pintype "passive"))
      (node (ref "T4") (pin "1") (pinfunction "G_1") (pintype "passive"))
    )
    (net (code "8") (name "/FPGA_INIT_B") (class "Default")
      (node (ref "IC4") (pin "U12") (pinfunction "INIT_B_0_U12") (pintype "bidirectional"))
      (node (ref "R53") (pin "2") (pinfunction "2_2") (pintype "passive"))
    )
    (net (code "9") (name "/RESETn") (class "Default")
      (node (ref "R53") (pin "1") (pinfunction "1_1") (pintype "passive"))
    )
    (net (code "10") (name "/XADC_GND") (class "Default")
      (node (ref "C50") (pin "1") (pinfunction "1_1") (pintype "passive"))
      (node (ref "C51") (pin "1") (pinfunction "1_1") (pintype "passive"))
      (node (ref "IC4") (pin "K9") (pinfunction "GNDADC_0_K9") (pintype "power_in"))
      (node (ref "IC4") (pin "L10") (pinfunction "VP_0_L10") (pintype "input"))
      (node (ref "IC4") (pin "L9") (pinfunction "VREFN_0_L9") (pintype "input"))
      (node (ref "IC4") (pin "M10") (pinfunction "VREFP_0_M10") (pintype "input"))
      (node (ref "IC4") (pin "M9") (pinfunction "VN_0_M9") (pintype "input"))
      (node (ref "L5") (pin "2") (pinfunction "2_2") (pintype "passive"))
    )
    (net (code "11") (name "/XADC_VCC") (class "Default")
      (node (ref "C50") (pin "2") (pinfunction "2_2") (pintype "passive"))
      (node (ref "C51") (pin "2") (pinfunction "2_2") (pintype "passive"))
      (node (ref "IC4") (pin "K10") (pinfunction "VCCADC_0_K10") (pintype "power_in"))
      (node (ref "L4") (pin "2") (pinfunction "2_2") (pintype "passive"))
    )
    (net (code "12") (name "GND") (class "Default")
      (node (ref "C100") (pin "1") (pinfunction "1_1") (pintype "passive"))
      (node (ref "C101") (pin "1") (pinfunction "1_1") (pintype "passive"))
      (node (ref "C102") (pin "1") (pinfunction "1_1") (pintype "passive"))
      (node (ref "C103") (pin "1") (pinfunction "1_1") (pintype "passive"))
      (node (ref "C104") (pin "1") (pinfunction "1_1") (pintype "passive"))
      (node (ref "C105") (pin "1") (pinfunction "1_1") (pintype "passive"))
      (node (ref "C106") (pin "1") (pinfunction "1_1") (pintype "passive"))
      (node (ref "C107") (pin "1") (pinfunction "1_1") (pintype "passive"))
      (node (ref "C108") (pin "1") (pinfunction "1_1") (pintype "passive"))
      (node (ref "C109") (pin "1") (pinfunction "1_1") (pintype "passive"))
      (node (ref "C110") (pin "1") (pinfunction "1_1") (pintype "passive"))
      (node (ref "C111") (pin "1") (pinfunction "1_1") (pintype "passive"))
      (node (ref "C112") (pin "1") (pinfunction "1_1") (pintype "passive"))
      (node (ref "C113") (pin "1") (pinfunction "1_1") (pintype "passive"))
      (node (ref "C114") (pin "1") (pinfunction "1_1") (pintype "passive"))
      (node (ref "C115") (pin "1") (pinfunction "1_1") (pintype "passive"))
      (node (ref "C116") (pin "1") (pinfunction "1_1") (pintype "passive"))
      (node (ref "C117") (pin "1") (pinfunction "1_1") (pintype "passive"))
      (node (ref "C118") (pin "1") (pinfunction "1_1") (pintype "passive"))
      (node (ref "C119") (pin "1") (pinfunction "1_1") (pintype "passive"))
      (node (ref "C120") (pin "1") (pinfunction "1_1") (pintype "passive"))
      (node (ref "C121") (pin "1") (pinfunction "1_1") (pintype "passive"))
      (node (ref "C122") (pin "1") (pinfunction "1_1") (pintype "passive"))
      (node (ref "C123") (pin "1") (pinfunction "1_1") (pintype "passive"))
      (node (ref "C124") (pin "1") (pinfunction "1_1") (pintype "passive"))
      (node (ref "C125") (pin "1") (pinfunction "1_1") (pintype "passive"))
      (node (ref "C235") (pin "1") (pinfunction "1_1") (pintype "passive"))
      (node (ref "C240") (pin "1") (pinfunction "1_1") (pintype "passive"))
      (node (ref "C52") (pin "1") (pinfunction "1_1") (pintype "passive"))
      (node (ref "C53") (pin "1") (pinfunction "1_1") (pintype "passive"))
      (node (ref "C54") (pin "1") (pinfunction "1_1") (pintype "passive"))
      (node (ref "C55") (pin "1") (pinfunction "1_1") (pintype "passive"))
      (node (ref "C56") (pin "1") (pinfunction "1_1") (pintype "passive"))
      (node (ref "C57") (pin "1") (pinfunction "1_1") (pintype "passive"))
      (node (ref "C58") (pin "1") (pinfunction "1_1") (pintype "passive"))
      (node (ref "C59") (pin "1") (pinfunction "1_1") (pintype "passive"))
      (node (ref "C60") (pin "1") (pinfunction "1_1") (pintype "passive"))
      (node (ref "C61") (pin "1") (pinfunction "1_1") (pintype "passive"))
      (node (ref "C62") (pin "1") (pinfunction "1_1") (pintype "passive"))
      (node (ref "C63") (pin "1") (pinfunction "1_1") (pintype "passive"))
      (node (ref "C64") (pin "1") (pinfunction "1_1") (pintype "passive"))
      (node (ref "C65") (pin "1") (pinfunction "1_1") (pintype "passive"))
      (node (ref "C66") (pin "1") (pinfunction "1_1") (pintype "passive"))
      (node (ref "C67") (pin "1") (pinfunction "1_1") (pintype "passive"))
      (node (ref "C68") (pin "1") (pinfunction "1_1") (pintype "passive"))
      (node (ref "C69") (pin "1") (pinfunction "1_1") (pintype "passive"))
      (node (ref "C70") (pin "1") (pinfunction "1_1") (pintype "passive"))
      (node (ref "C71") (pin "1") (pinfunction "1_1") (pintype "passive"))
      (node (ref "C72") (pin "1") (pinfunction "1_1") (pintype "passive"))
      (node (ref "C73") (pin "1") (pinfunction "1_1") (pintype "passive"))
      (node (ref "C74") (pin "1") (pinfunction "1_1") (pintype "passive"))
      (node (ref "C75") (pin "1") (pinfunction "1_1") (pintype "passive"))
      (node (ref "C76") (pin "1") (pinfunction "1_1") (pintype "passive"))
      (node (ref "C77") (pin "1") (pinfunction "1_1") (pintype "passive"))
      (node (ref "C78") (pin "1") (pinfunction "1_1") (pintype "passive"))
      (node (ref "C79") (pin "1") (pinfunction "1_1") (pintype "passive"))
      (node (ref "C80") (pin "1") (pinfunction "1_1") (pintype "passive"))
      (node (ref "C81") (pin "1") (pinfunction "1_1") (pintype "passive"))
      (node (ref "C82") (pin "1") (pinfunction "1_1") (pintype "passive"))
      (node (ref "C83") (pin "1") (pinfunction "1_1") (pintype "passive"))
      (node (ref "C84") (pin "1") (pinfunction "1_1") (pintype "passive"))
      (node (ref "C85") (pin "1") (pinfunction "1_1") (pintype "passive"))
      (node (ref "C86") (pin "1") (pinfunction "1_1") (pintype "passive"))
      (node (ref "C87") (pin "1") (pinfunction "1_1") (pintype "passive"))
      (node (ref "C88") (pin "1") (pinfunction "1_1") (pintype "passive"))
      (node (ref "C89") (pin "1") (pinfunction "1_1") (pintype "passive"))
      (node (ref "C90") (pin "1") (pinfunction "1_1") (pintype "passive"))
      (node (ref "C91") (pin "2") (pinfunction "2_2") (pintype "passive"))
      (node (ref "C92") (pin "1") (pinfunction "1_1") (pintype "passive"))
      (node (ref "C93") (pin "1") (pinfunction "1_1") (pintype "passive"))
      (node (ref "C94") (pin "1") (pinfunction "1_1") (pintype "passive"))
      (node (ref "C95") (pin "1") (pinfunction "1_1") (pintype "passive"))
      (node (ref "C96") (pin "1") (pinfunction "1_1") (pintype "passive"))
      (node (ref "C97") (pin "1") (pinfunction "1_1") (pintype "passive"))
      (node (ref "C98") (pin "1") (pinfunction "1_1") (pintype "passive"))
      (node (ref "C99") (pin "1") (pinfunction "1_1") (pintype "passive"))
      (node (ref "D15") (pin "1") (pinfunction "GND_1") (pintype "power_in"))
      (node (ref "D16") (pin "1") (pinfunction "GND_1") (pintype "power_in"))
      (node (ref "IC4") (pin "A11") (pinfunction "GND_A11") (pintype "power_in"))
      (node (ref "IC4") (pin "A12") (pinfunction "GND_A12") (pintype "power_in"))
      (node (ref "IC4") (pin "A2") (pinfunction "GND_A2") (pintype "power_in"))
      (node (ref "IC4") (pin "A22") (pinfunction "GND_A22") (pintype "power_in"))
      (node (ref "IC4") (pin "A3") (pinfunction "GND_A3") (pintype "power_in"))
      (node (ref "IC4") (pin "A5") (pinfunction "GND_A5") (pintype "power_in"))
      (node (ref "IC4") (pin "A7") (pinfunction "GND_A7") (pintype "power_in"))
      (node (ref "IC4") (pin "A9") (pinfunction "GND_A9") (pintype "power_in"))
      (node (ref "IC4") (pin "AA12") (pinfunction "GND_AA12") (pintype "power_in"))
      (node (ref "IC4") (pin "AA2") (pinfunction "GND_AA2") (pintype "power_in"))
      (node (ref "IC4") (pin "AA22") (pinfunction "GND_AA22") (pintype "power_in"))
      (node (ref "IC4") (pin "AB19") (pinfunction "GND_AB19") (pintype "power_in"))
      (node (ref "IC4") (pin "AB9") (pinfunction "GND_AB9") (pintype "power_in"))
      (node (ref "IC4") (pin "B12") (pinfunction "GND_B12") (pintype "power_in"))
      (node (ref "IC4") (pin "B19") (pinfunction "GND_B19") (pintype "power_in"))
      (node (ref "IC4") (pin "B3") (pinfunction "GND_B3") (pintype "power_in"))
      (node (ref "IC4") (pin "C10") (pinfunction "GND_C10") (pintype "power_in"))
      (node (ref "IC4") (pin "C12") (pinfunction "GND_C12") (pintype "power_in"))
      (node (ref "IC4") (pin "C16") (pinfunction "GND_C16") (pintype "power_in"))
      (node (ref "IC4") (pin "C3") (pinfunction "GND_C3") (pintype "power_in"))
      (node (ref "IC4") (pin "C6") (pinfunction "GND_C6") (pintype "power_in"))
      (node (ref "IC4") (pin "D12") (pinfunction "GND_D12") (pintype "power_in"))
      (node (ref "IC4") (pin "D13") (pinfunction "GND_D13") (pintype "power_in"))
      (node (ref "IC4") (pin "D3") (pinfunction "GND_D3") (pintype "power_in"))
      (node (ref "IC4") (pin "D4") (pinfunction "GND_D4") (pintype "power_in"))
      (node (ref "IC4") (pin "D8") (pinfunction "GND_D8") (pintype "power_in"))
      (node (ref "IC4") (pin "E11") (pinfunction "GND_E11") (pintype "power_in"))
      (node (ref "IC4") (pin "E12") (pinfunction "VCCBATT_0_E12") (pintype "power_in"))
      (node (ref "IC4") (pin "E20") (pinfunction "GND_E20") (pintype "power_in"))
      (node (ref "IC4") (pin "E4") (pinfunction "GND_E4") (pintype "power_in"))
      (node (ref "IC4") (pin "E5") (pinfunction "GND_E5") (pintype "power_in"))
      (node (ref "IC4") (pin "E7") (pinfunction "GND_E7") (pintype "power_in"))
      (node (ref "IC4") (pin "E9") (pinfunction "GND_E9") (pintype "power_in"))
      (node (ref "IC4") (pin "F11") (pinfunction "GND_F11") (pintype "power_in"))
      (node (ref "IC4") (pin "F17") (pinfunction "GND_F17") (pintype "power_in"))
      (node (ref "IC4") (pin "F5") (pinfunction "GND_F5") (pintype "power_in"))
      (node (ref "IC4") (pin "G10") (pinfunction "GND_G10") (pintype "power_in"))
      (node (ref "IC4") (pin "G12") (pinfunction "GND_G12") (pintype "power_in"))
      (node (ref "IC4") (pin "G14") (pinfunction "GND_G14") (pintype "power_in"))
      (node (ref "IC4") (pin "G5") (pinfunction "GND_G5") (pintype "power_in"))
      (node (ref "IC4") (pin "G6") (pinfunction "GND_G6") (pintype "power_in"))
      (node (ref "IC4") (pin "G7") (pinfunction "GND_G7") (pintype "power_in"))
      (node (ref "IC4") (pin "G8") (pinfunction "GND_G8") (pintype "power_in"))
      (node (ref "IC4") (pin "G9") (pinfunction "GND_G9") (pintype "power_in"))
      (node (ref "IC4") (pin "H1") (pinfunction "GND_H1") (pintype "power_in"))
      (node (ref "IC4") (pin "H11") (pinfunction "GND_H11") (pintype "power_in"))
      (node (ref "IC4") (pin "H21") (pinfunction "GND_H21") (pintype "power_in"))
      (node (ref "IC4") (pin "H7") (pinfunction "GND_H7") (pintype "power_in"))
      (node (ref "IC4") (pin "H9") (pinfunction "GND_H9") (pintype "power_in"))
      (node (ref "IC4") (pin "J10") (pinfunction "GND_J10") (pintype "power_in"))
      (node (ref "IC4") (pin "J12") (pinfunction "GND_J12") (pintype "power_in"))
      (node (ref "IC4") (pin "J18") (pinfunction "GND_J18") (pintype "power_in"))
      (node (ref "IC4") (pin "J8") (pinfunction "GND_J8") (pintype "power_in"))
      (node (ref "IC4") (pin "K11") (pinfunction "GND_K11") (pintype "power_in"))
      (node (ref "IC4") (pin "K15") (pinfunction "GND_K15") (pintype "power_in"))
      (node (ref "IC4") (pin "K5") (pinfunction "GND_K5") (pintype "power_in"))
      (node (ref "IC4") (pin "K7") (pinfunction "GND_K7") (pintype "power_in"))
      (node (ref "IC4") (pin "L2") (pinfunction "GND_L2") (pintype "power_in"))
      (node (ref "IC4") (pin "L22") (pinfunction "GND_L22") (pintype "power_in"))
      (node (ref "IC4") (pin "L8") (pinfunction "GND_L8") (pintype "power_in"))
      (node (ref "IC4") (pin "M11") (pinfunction "GND_M11") (pintype "power_in"))
      (node (ref "IC4") (pin "M19") (pinfunction "GND_M19") (pintype "power_in"))
      (node (ref "IC4") (pin "M7") (pinfunction "GND_M7") (pintype "power_in"))
      (node (ref "IC4") (pin "N10") (pinfunction "DXP_0_N10") (pintype "input"))
      (node (ref "IC4") (pin "N16") (pinfunction "GND_N16") (pintype "power_in"))
      (node (ref "IC4") (pin "N6") (pinfunction "GND_N6") (pintype "power_in"))
      (node (ref "IC4") (pin "N8") (pinfunction "GND_N8") (pintype "power_in"))
      (node (ref "IC4") (pin "N9") (pinfunction "DXN_0_N9") (pintype "input"))
      (node (ref "IC4") (pin "P11") (pinfunction "GND_P11") (pintype "power_in"))
      (node (ref "IC4") (pin "P13") (pinfunction "GND_P13") (pintype "power_in"))
      (node (ref "IC4") (pin "P3") (pinfunction "GND_P3") (pintype "power_in"))
      (node (ref "IC4") (pin "P7") (pinfunction "GND_P7") (pintype "power_in"))
      (node (ref "IC4") (pin "P9") (pinfunction "GND_P9") (pintype "power_in"))
      (node (ref "IC4") (pin "R10") (pinfunction "GND_R10") (pintype "power_in"))
      (node (ref "IC4") (pin "R12") (pinfunction "GND_R12") (pintype "power_in"))
      (node (ref "IC4") (pin "R20") (pinfunction "GND_R20") (pintype "power_in"))
      (node (ref "IC4") (pin "R8") (pinfunction "GND_R8") (pintype "power_in"))
      (node (ref "IC4") (pin "T11") (pinfunction "GND_T11") (pintype "power_in"))
      (node (ref "IC4") (pin "T17") (pinfunction "GND_T17") (pintype "power_in"))
      (node (ref "IC4") (pin "T7") (pinfunction "GND_T7") (pintype "power_in"))
      (node (ref "IC4") (pin "T9") (pinfunction "GND_T9") (pintype "power_in"))
      (node (ref "IC4") (pin "U10") (pinfunction "M1_0_U10") (pintype "input"))
      (node (ref "IC4") (pin "U14") (pinfunction "GND_U14") (pintype "power_in"))
      (node (ref "IC4") (pin "U4") (pinfunction "GND_U4") (pintype "power_in"))
      (node (ref "IC4") (pin "U9") (pinfunction "M2_0_U9") (pintype "input"))
      (node (ref "IC4") (pin "V1") (pinfunction "GND_V1") (pintype "power_in"))
      (node (ref "IC4") (pin "V11") (pinfunction "GND_V11") (pintype "power_in"))
      (node (ref "IC4") (pin "V21") (pinfunction "GND_V21") (pintype "power_in"))
      (node (ref "IC4") (pin "W18") (pinfunction "GND_W18") (pintype "power_in"))
      (node (ref "IC4") (pin "W8") (pinfunction "GND_W8") (pintype "power_in"))
      (node (ref "IC4") (pin "Y15") (pinfunction "GND_Y15") (pintype "power_in"))
      (node (ref "IC4") (pin "Y5") (pinfunction "GND_Y5") (pintype "power_in"))
      (node (ref "J8") (pin "1") (pinfunction "1_1") (pintype "bidirectional"))
      (node (ref "J8") (pin "11") (pinfunction "11_11") (pintype "bidirectional"))
      (node (ref "J8") (pin "3") (pinfunction "3_3") (pintype "bidirectional"))
      (node (ref "J8") (pin "5") (pinfunction "5_5") (pintype "bidirectional"))
      (node (ref "J8") (pin "7") (pinfunction "7_7") (pintype "bidirectional"))
      (node (ref "J8") (pin "9") (pinfunction "9_9") (pintype "bidirectional"))
      (node (ref "L5") (pin "1") (pinfunction "1_1") (pintype "passive"))
      (node (ref "T4") (pin "2") (pinfunction "S_2") (pintype "passive"))
    )
    (net (code "13") (name "MGTAVCC") (class "Default")
      (node (ref "C100") (pin "2") (pinfunction "2_2") (pintype "passive"))
      (node (ref "C123") (pin "2") (pinfunction "2_2") (pintype "passive"))
      (node (ref "C124") (pin "2") (pinfunction "2_2") (pintype "passive"))
      (node (ref "C125") (pin "2") (pinfunction "2_2") (pintype "passive"))
      (node (ref "C57") (pin "2") (pinfunction "2_2") (pintype "passive"))
      (node (ref "IC4") (pin "D10") (pinfunction "MGTAVCC_D10") (pintype "power_in"))
      (node (ref "IC4") (pin "D6") (pinfunction "MGTAVCC_D6") (pintype "power_in"))
      (node (ref "IC4") (pin "E8") (pinfunction "MGTAVCC_E8") (pintype "power_in"))
      (node (ref "IC4") (pin "F7") (pinfunction "MGTAVCC_F7") (pintype "power_in"))
      (node (ref "IC4") (pin "F9") (pinfunction "MGTAVCC_F9") (pintype "power_in"))
    )
    (net (code "14") (name "MGTAVTT") (class "Default")
      (node (ref "C101") (pin "2") (pinfunction "2_2") (pintype "passive"))
      (node (ref "C112") (pin "2") (pinfunction "2_2") (pintype "passive"))
      (node (ref "C113") (pin "2") (pinfunction "2_2") (pintype "passive"))
      (node (ref "C114") (pin "2") (pinfunction "2_2") (pintype "passive"))
      (node (ref "C115") (pin "2") (pinfunction "2_2") (pintype "passive"))
      (node (ref "C116") (pin "2") (pinfunction "2_2") (pintype "passive"))
      (node (ref "C97") (pin "2") (pinfunction "2_2") (pintype "passive"))
      (node (ref "IC4") (pin "B11") (pinfunction "MGTAVTT_B11") (pintype "power_in"))
      (node (ref "IC4") (pin "B5") (pinfunction "MGTAVTT_B5") (pintype "power_in"))
      (node (ref "IC4") (pin "B7") (pinfunction "MGTAVTT_B7") (pintype "power_in"))
      (node (ref "IC4") (pin "B9") (pinfunction "MGTAVTT_B9") (pintype "power_in"))
      (node (ref "IC4") (pin "C4") (pinfunction "MGTAVTT_C4") (pintype "power_in"))
      (node (ref "IC4") (pin "C8") (pinfunction "MGTAVTT_C8") (pintype "power_in"))
    )
    (net (code "15") (name "Net-(IC4G-PROGRAM_B_0)") (class "Default")
      (node (ref "IC4") (pin "N12") (pinfunction "PROGRAM_B_0_N12") (pintype "input"))
      (node (ref "R52") (pin "2") (pinfunction "2_2") (pintype "passive"))
    )
    (net (code "16") (name "Net-(LD3-A)") (class "Default")
      (node (ref "LD3") (pin "2") (pinfunction "A_2") (pintype "passive"))
      (node (ref "R55") (pin "1") (pinfunction "1_1") (pintype "passive"))
    )
    (net (code "17") (name "Net-(LD3-C)") (class "Default")
      (node (ref "LD3") (pin "1") (pinfunction "C_1") (pintype "passive"))
      (node (ref "T4") (pin "3") (pinfunction "D_3") (pintype "passive"))
    )
    (net (code "18") (name "P1V0") (class "Default")
      (node (ref "C102") (pin "2") (pinfunction "2_2") (pintype "passive"))
      (node (ref "C103") (pin "2") (pinfunction "2_2") (pintype "passive"))
      (node (ref "C104") (pin "2") (pinfunction "2_2") (pintype "passive"))
      (node (ref "C105") (pin "2") (pinfunction "2_2") (pintype "passive"))
      (node (ref "C106") (pin "2") (pinfunction "2_2") (pintype "passive"))
      (node (ref "C107") (pin "2") (pinfunction "2_2") (pintype "passive"))
      (node (ref "C108") (pin "2") (pinfunction "2_2") (pintype "passive"))
      (node (ref "C109") (pin "2") (pinfunction "2_2") (pintype "passive"))
      (node (ref "C110") (pin "2") (pinfunction "2_2") (pintype "passive"))
      (node (ref "C91") (pin "1") (pinfunction "1_1") (pintype "passive"))
      (node (ref "C92") (pin "2") (pinfunction "2_2") (pintype "passive"))
      (node (ref "C93") (pin "2") (pinfunction "2_2") (pintype "passive"))
      (node (ref "C94") (pin "2") (pinfunction "2_2") (pintype "passive"))
      (node (ref "C95") (pin "2") (pinfunction "2_2") (pintype "passive"))
      (node (ref "C96") (pin "2") (pinfunction "2_2") (pintype "passive"))
      (node (ref "IC4") (pin "H10") (pinfunction "VCCINT_H10") (pintype "power_in"))
      (node (ref "IC4") (pin "H8") (pinfunction "VCCINT_H8") (pintype "power_in"))
      (node (ref "IC4") (pin "J7") (pinfunction "VCCINT_J7") (pintype "power_in"))
      (node (ref "IC4") (pin "J9") (pinfunction "VCCINT_J9") (pintype "power_in"))
      (node (ref "IC4") (pin "K8") (pinfunction "VCCINT_K8") (pintype "power_in"))
      (node (ref "IC4") (pin "L7") (pinfunction "VCCINT_L7") (pintype "power_in"))
      (node (ref "IC4") (pin "M8") (pinfunction "VCCINT_M8") (pintype "power_in"))
      (node (ref "IC4") (pin "N7") (pinfunction "VCCINT_N7") (pintype "power_in"))
      (node (ref "IC4") (pin "P10") (pinfunction "VCCINT_P10") (pintype "power_in"))
      (node (ref "IC4") (pin "P8") (pinfunction "VCCINT_P8") (pintype "power_in"))
      (node (ref "IC4") (pin "R7") (pinfunction "VCCINT_R7") (pintype "power_in"))
      (node (ref "IC4") (pin "R9") (pinfunction "VCCINT_R9") (pintype "power_in"))
      (node (ref "IC4") (pin "T10") (pinfunction "VCCINT_T10") (pintype "power_in"))
      (node (ref "IC4") (pin "T8") (pinfunction "VCCINT_T8") (pintype "power_in"))
    )
    (net (code "19") (name "P1V5") (class "Default")
      (node (ref "C240") (pin "2") (pinfunction "2_2") (pintype "passive"))
      (node (ref "C60") (pin "2") (pinfunction "2_2") (pintype "passive"))
      (node (ref "C64") (pin "2") (pinfunction "2_2") (pintype "passive"))
      (node (ref "C81") (pin "2") (pinfunction "2_2") (pintype "passive"))
      (node (ref "C82") (pin "2") (pinfunction "2_2") (pintype "passive"))
      (node (ref "C83") (pin "2") (pinfunction "2_2") (pintype "passive"))
      (node (ref "C84") (pin "2") (pinfunction "2_2") (pintype "passive"))
      (node (ref "C85") (pin "2") (pinfunction "2_2") (pintype "passive"))
      (node (ref "IC4") (pin "C1") (pinfunction "VCCO_35_C1") (pintype "power_in"))
      (node (ref "IC4") (pin "F2") (pinfunction "VCCO_35_F2") (pintype "power_in"))
      (node (ref "IC4") (pin "H6") (pinfunction "VCCO_35_H6") (pintype "power_in"))
      (node (ref "IC4") (pin "J3") (pinfunction "VCCO_35_J3") (pintype "power_in"))
      (node (ref "IC4") (pin "M4") (pinfunction "VCCO_35_M4") (pintype "power_in"))
      (node (ref "IC4") (pin "N1") (pinfunction "VCCO_35_N1") (pintype "power_in"))
    )
    (net (code "20") (name "P1V8") (class "Default")
      (node (ref "L4") (pin "1") (pinfunction "1_1") (pintype "passive"))
    )
    (net (code "21") (name "P2V5") (class "Default")
      (node (ref "C52") (pin "2") (pinfunction "2_2") (pintype "passive"))
      (node (ref "C54") (pin "2") (pinfunction "2_2") (pintype "passive"))
      (node (ref "C58") (pin "2") (pinfunction "2_2") (pintype "passive"))
      (node (ref "C61") (pin "2") (pinfunction "2_2") (pintype "passive"))
      (node (ref "C62") (pin "2") (pinfunction "2_2") (pintype "passive"))
      (node (ref "C63") (pin "2") (pinfunction "2_2") (pintype "passive"))
      (node (ref "C65") (pin "2") (pinfunction "2_2") (pintype "passive"))
      (node (ref "C66") (pin "2") (pinfunction "2_2") (pintype "passive"))
      (node (ref "C67") (pin "2") (pinfunction "2_2") (pintype "passive"))
      (node (ref "C68") (pin "2") (pinfunction "2_2") (pintype "passive"))
      (node (ref "C69") (pin "2") (pinfunction "2_2") (pintype "passive"))
      (node (ref "C70") (pin "2") (pinfunction "2_2") (pintype "passive"))
      (node (ref "C71") (pin "2") (pinfunction "2_2") (pintype "passive"))
      (node (ref "C72") (pin "2") (pinfunction "2_2") (pintype "passive"))
      (node (ref "C73") (pin "2") (pinfunction "2_2") (pintype "passive"))
      (node (ref "C74") (pin "2") (pinfunction "2_2") (pintype "passive"))
      (node (ref "C75") (pin "2") (pinfunction "2_2") (pintype "passive"))
      (node (ref "C76") (pin "2") (pinfunction "2_2") (pintype "passive"))
      (node (ref "C77") (pin "2") (pinfunction "2_2") (pintype "passive"))
      (node (ref "C78") (pin "2") (pinfunction "2_2") (pintype "passive"))
      (node (ref "C79") (pin "2") (pinfunction "2_2") (pintype "passive"))
      (node (ref "C80") (pin "2") (pinfunction "2_2") (pintype "passive"))
      (node (ref "C86") (pin "2") (pinfunction "2_2") (pintype "passive"))
      (node (ref "C87") (pin "2") (pinfunction "2_2") (pintype "passive"))
      (node (ref "C88") (pin "2") (pinfunction "2_2") (pintype "passive"))
      (node (ref "C89") (pin "2") (pinfunction "2_2") (pintype "passive"))
      (node (ref "C90") (pin "2") (pinfunction "2_2") (pintype "passive"))
      (node (ref "D15") (pin "4") (pinfunction "VCC_4") (pintype "power_in"))
      (node (ref "D16") (pin "4") (pinfunction "VCC_4") (pintype "power_in"))
      (node (ref "IC4") (pin "A17") (pinfunction "VCCO_16_A17") (pintype "power_in"))
      (node (ref "IC4") (pin "AA17") (pinfunction "VCCO_13_AA17") (pintype "power_in"))
      (node (ref "IC4") (pin "AA7") (pinfunction "VCCO_34_AA7") (pintype "power_in"))
      (node (ref "IC4") (pin "AB14") (pinfunction "VCCO_13_AB14") (pintype "power_in"))
      (node (ref "IC4") (pin "AB4") (pinfunction "VCCO_34_AB4") (pintype "power_in"))
      (node (ref "IC4") (pin "B14") (pinfunction "VCCO_16_B14") (pintype "power_in"))
      (node (ref "IC4") (pin "C21") (pinfunction "VCCO_16_C21") (pintype "power_in"))
      (node (ref "IC4") (pin "D18") (pinfunction "VCCO_16_D18") (pintype "power_in"))
      (node (ref "IC4") (pin "E15") (pinfunction "VCCO_16_E15") (pintype "power_in"))
      (node (ref "IC4") (pin "F12") (pinfunction "VCCO_0_F12") (pintype "power_in"))
      (node (ref "IC4") (pin "F22") (pinfunction "VCCO_16_F22") (pintype "power_in"))
      (node (ref "IC4") (pin "G19") (pinfunction "VCCO_15_G19") (pintype "power_in"))
      (node (ref "IC4") (pin "H16") (pinfunction "VCCO_15_H16") (pintype "power_in"))
      (node (ref "IC4") (pin "J13") (pinfunction "VCCO_15_J13") (pintype "power_in"))
      (node (ref "IC4") (pin "K20") (pinfunction "VCCO_15_K20") (pintype "power_in"))
      (node (ref "IC4") (pin "L17") (pinfunction "VCCO_15_L17") (pintype "power_in"))
      (node (ref "IC4") (pin "M14") (pinfunction "VCCO_14_M14") (pintype "power_in"))
      (node (ref "IC4") (pin "N21") (pinfunction "VCCO_15_N21") (pintype "power_in"))
      (node (ref "IC4") (pin "P18") (pinfunction "VCCO_14_P18") (pintype "power_in"))
      (node (ref "IC4") (pin "R15") (pinfunction "VCCO_14_R15") (pintype "power_in"))
      (node (ref "IC4") (pin "R5") (pinfunction "VCCO_34_R5") (pintype "power_in"))
      (node (ref "IC4") (pin "T12") (pinfunction "VCCO_0_T12") (pintype "power_in"))
      (node (ref "IC4") (pin "T2") (pinfunction "VCCO_34_T2") (pintype "power_in"))
      (node (ref "IC4") (pin "T22") (pinfunction "VCCO_14_T22") (pintype "power_in"))
      (node (ref "IC4") (pin "U11") (pinfunction "M0_0_U11") (pintype "input"))
      (node (ref "IC4") (pin "U19") (pinfunction "VCCO_14_U19") (pintype "power_in"))
      (node (ref "IC4") (pin "U8") (pinfunction "CFGBVS_0_U8") (pintype "input"))
      (node (ref "IC4") (pin "V16") (pinfunction "VCCO_13_V16") (pintype "power_in"))
      (node (ref "IC4") (pin "V6") (pinfunction "VCCO_34_V6") (pintype "power_in"))
      (node (ref "IC4") (pin "W13") (pinfunction "VCCO_13_W13") (pintype "power_in"))
      (node (ref "IC4") (pin "W3") (pinfunction "VCCO_34_W3") (pintype "power_in"))
      (node (ref "IC4") (pin "Y10") (pinfunction "VCCO_13_Y10") (pintype "power_in"))
      (node (ref "IC4") (pin "Y20") (pinfunction "VCCO_14_Y20") (pintype "power_in"))
      (node (ref "J8") (pin "2") (pinfunction "2_2") (pintype "bidirectional"))
      (node (ref "R52") (pin "1") (pinfunction "1_1") (pintype "passive"))
      (node (ref "R57") (pin "2") (pinfunction "2_2") (pintype "passive"))
      (node (ref "R58") (pin "2") (pinfunction "2_2") (pintype "passive"))
    )
    (net (code "22") (name "P3V3") (class "Default")
      (node (ref "R55") (pin "2") (pinfunction "2_2") (pintype "passive"))
    )
    (net (code "23") (name "VCCAUX") (class "Default")
      (node (ref "C111") (pin "2") (pinfunction "2_2") (pintype "passive"))
      (node (ref "C117") (pin "2") (pinfunction "2_2") (pintype "passive"))
      (node (ref "C118") (pin "2") (pinfunction "2_2") (pintype "passive"))
      (node (ref "C119") (pin "2") (pinfunction "2_2") (pintype "passive"))
      (node (ref "C235") (pin "2") (pinfunction "2_2") (pintype "passive"))
      (node (ref "C55") (pin "2") (pinfunction "2_2") (pintype "passive"))
      (node (ref "C59") (pin "2") (pinfunction "2_2") (pintype "passive"))
      (node (ref "C98") (pin "2") (pinfunction "2_2") (pintype "passive"))
      (node (ref "IC4") (pin "H12") (pinfunction "VCCAUX_H12") (pintype "power_in"))
      (node (ref "IC4") (pin "K12") (pinfunction "VCCAUX_K12") (pintype "power_in"))
      (node (ref "IC4") (pin "M12") (pinfunction "VCCAUX_M12") (pintype "power_in"))
      (node (ref "IC4") (pin "P12") (pinfunction "VCCAUX_P12") (pintype "power_in"))
      (node (ref "IC4") (pin "R11") (pinfunction "VCCAUX_R11") (pintype "power_in"))
    )
    (net (code "24") (name "VCCBRAM") (class "Default")
      (node (ref "C120") (pin "2") (pinfunction "2_2") (pintype "passive"))
      (node (ref "C121") (pin "2") (pinfunction "2_2") (pintype "passive"))
      (node (ref "C122") (pin "2") (pinfunction "2_2") (pintype "passive"))
      (node (ref "C56") (pin "2") (pinfunction "2_2") (pintype "passive"))
      (node (ref "C99") (pin "2") (pinfunction "2_2") (pintype "passive"))
      (node (ref "IC4") (pin "J11") (pinfunction "VCCBRAM_J11") (pintype "power_in"))
      (node (ref "IC4") (pin "L11") (pinfunction "VCCBRAM_L11") (pintype "power_in"))
      (node (ref "IC4") (pin "N11") (pinfunction "VCCBRAM_N11") (pintype "power_in"))
    )
    (net (code "25") (name "unconnected-(J8-Pad12)") (class "Default")
      (node (ref "J8") (pin "12") (pinfunction "12_12") (pintype "bidirectional+no_connect"))
    )
    (net (code "26") (name "unconnected-(J8-Pad14)") (class "Default")
      (node (ref "J8") (pin "14") (pinfunction "14_14") (pintype "bidirectional+no_connect"))
    )
  )
)
